# Power.net
KiCad netlist of a schematic drawn in Altium Designer
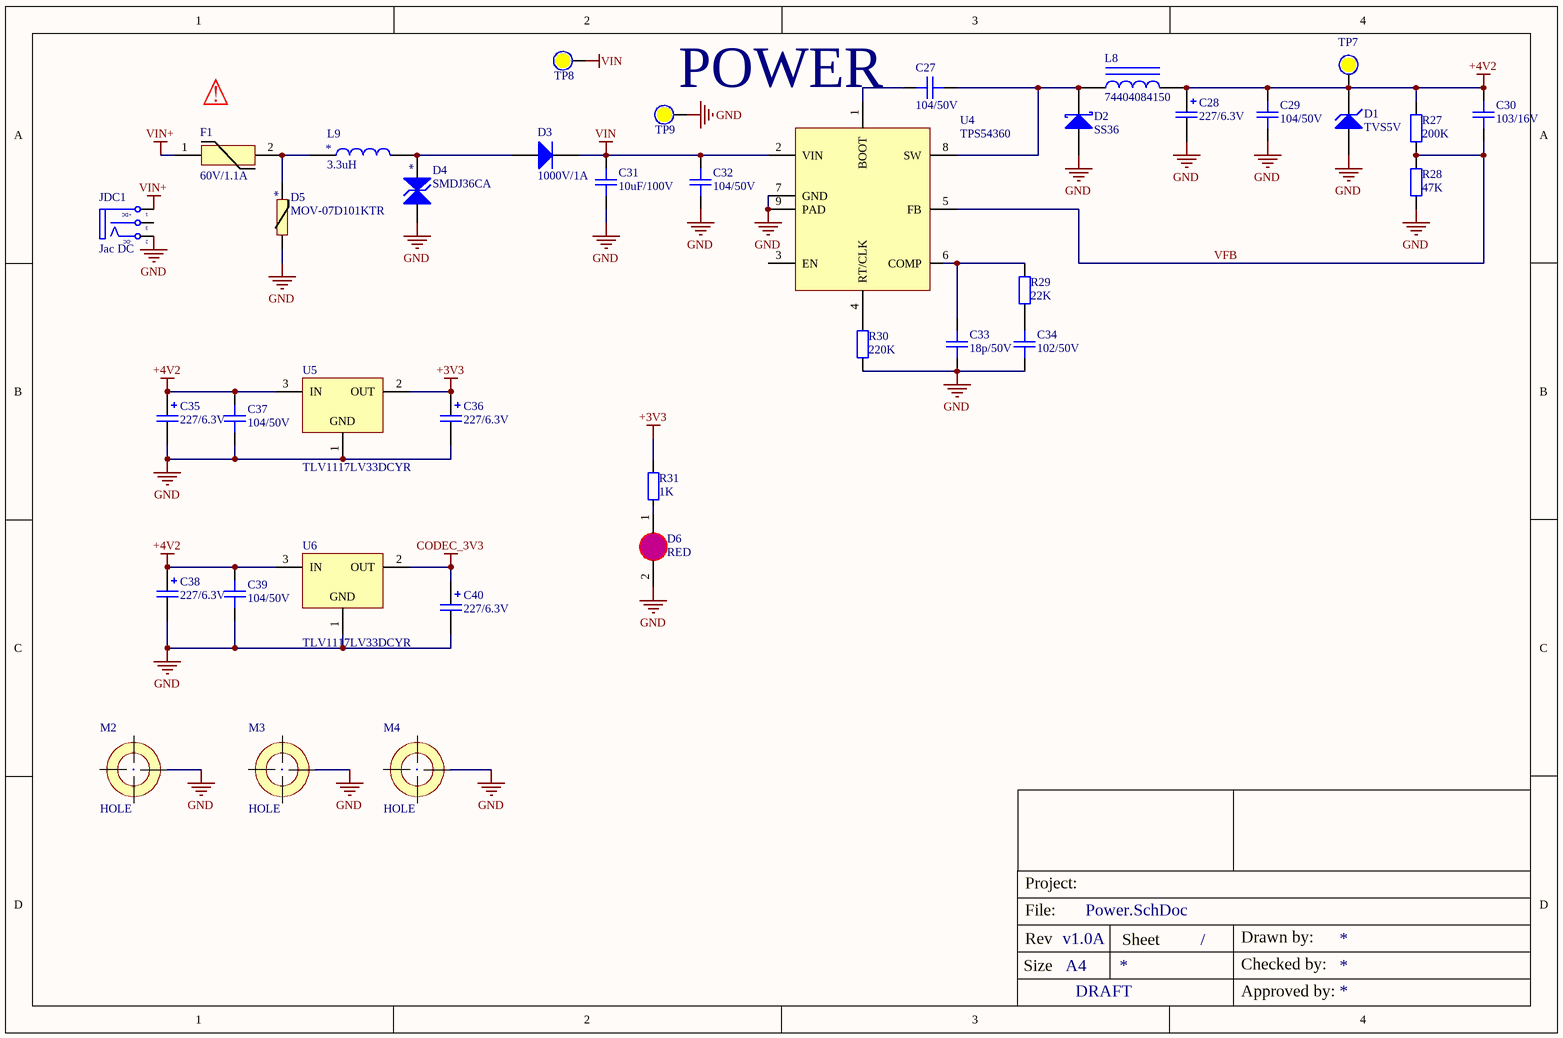
[diagram p0: Power.SchDoc]

(export (version "E")
  (design (tool "Eeschema 10.0.6"))
  (components
    (comp (ref "C27")
      (value "104/50V")
      (footprint "CAPC-0603 (1608)")
      (description "CAP CER 0.1uF 50V 10% X7R 0603")
      (fields (field (name "MPN") "C0603C104K5RACTU"))
      (libsource (lib "01.Passives") (part "C0603C104K5RACTU"))
    )
    (comp (ref "C28")
      (value "227/6.3V")
      (footprint "CAP_TANTAL_1210(3528)")
      (description "CAP TANT POLY 220uF 20% 6.3V 3528 35mOhm ESR")
      (fields (field (name "MPN") "T520B227M006ATE035"))
      (libsource (lib "01.Passives") (part "T520B227M006ATE035"))
    )
    (comp (ref "C29")
      (value "104/50V")
      (footprint "CAPC-0603 (1608)")
      (description "CAP CER 0.1uF 50V 10% X7R 0603")
      (fields (field (name "MPN") "C0603C104K5RACTU"))
      (libsource (lib "01.Passives") (part "C0603C104K5RACTU"))
    )
    (comp (ref "C30")
      (value "103/16V")
      (footprint "CAPC-0603 (1608)")
      (description "CAP CER 10nF 16V 10% X7R 0603")
      (fields (field (name "MPN") "CC0603KRX7R7BB103"))
      (libsource (lib "01.Passives") (part "CC0603KRX7R7BB103"))
    )
    (comp (ref "C31")
      (value "10uF/100V")
      (footprint "CAPC-2220 (5750)")
      (description "CAP CER 10UF 100V X7R 2220")
      (fields (field (name "MPN") "22201C106MAT2A") (field (name "MFR") "AVX Corporation"))
      (libsource (lib "01.Passives") (part "22201C106MAT2A"))
    )
    (comp (ref "C32")
      (value "104/50V")
      (footprint "CAPC-0603 (1608)")
      (description "CAP CER 0.1uF 50V 10% X7R 0603")
      (fields (field (name "MPN") "C0603C104K5RACTU"))
      (libsource (lib "01.Passives") (part "C0603C104K5RACTU"))
    )
    (comp (ref "C33")
      (value "18p/50V")
      (footprint "CAPC-0603 (1608)")
      (description "CAP CER 18pF 5% 50V C0G/NP0 0603")
      (fields (field (name "MPN") "CL10C180JB8NNNC"))
      (libsource (lib "01.Passives") (part "CL10C180JB8NNNC"))
    )
    (comp (ref "C34")
      (value "102/50V")
      (footprint "CAPC-0603 (1608)")
      (description "CAP CER 1nF 50V 10% X7R 0603")
      (fields (field (name "MPN") "C0603C102K5RACTU"))
      (libsource (lib "01.Passives") (part "C0603C102K5RACTU"))
    )
    (comp (ref "C35")
      (value "227/6.3V")
      (footprint "CAP_TANTAL_1210(3528)")
      (description "CAP TANT POLY 220uF 20% 6.3V 3528 35mOhm ESR")
      (fields (field (name "MPN") "T520B227M006ATE035"))
      (libsource (lib "lib") (part "T520B227M006ATE035"))
    )
    (comp (ref "C36")
      (value "227/6.3V")
      (footprint "CAP_TANTAL_1210(3528)")
      (description "CAP TANT POLY 220uF 20% 6.3V 3528 35mOhm ESR")
      (fields (field (name "MPN") "T520B227M006ATE035"))
      (libsource (lib "lib") (part "T520B227M006ATE035"))
    )
    (comp (ref "C37")
      (value "104/50V")
      (footprint "CAPC-0603 (1608)")
      (description "CAP CER 0.1uF 50V 10% X7R 0603")
      (fields (field (name "MPN") "C0603C104K5RACTU"))
      (libsource (lib "lib") (part "C0603C104K5RACTU"))
    )
    (comp (ref "C38")
      (value "227/6.3V")
      (footprint "CAP_TANTAL_1210(3528)")
      (description "CAP TANT POLY 220uF 20% 6.3V 3528 35mOhm ESR")
      (fields (field (name "MPN") "T520B227M006ATE035"))
      (libsource (lib "lib") (part "T520B227M006ATE035"))
    )
    (comp (ref "C39")
      (value "104/50V")
      (footprint "CAPC-0603 (1608)")
      (description "CAP CER 0.1uF 50V 10% X7R 0603")
      (fields (field (name "MPN") "C0603C104K5RACTU"))
      (libsource (lib "lib") (part "C0603C104K5RACTU"))
    )
    (comp (ref "C40")
      (value "227/6.3V")
      (footprint "CAP_TANTAL_1210(3528)")
      (description "CAP TANT POLY 220uF 20% 6.3V 3528 35mOhm ESR")
      (fields (field (name "MPN") "T520B227M006ATE035"))
      (libsource (lib "lib") (part "T520B227M006ATE035"))
    )
    (comp (ref "D1")
      (value "TVS5V")
      (footprint "DIODE_DO214AC_SMA")
      (description "DIODE TVS 5VWM 9.2VC SMA")
      (fields (field (name "MPN") "SMAJ5.0A-E3/61"))
      (libsource (lib "03.Semiconductor") (part "SMAJ5.0A-E3/61"))
    )
    (comp (ref "D2")
      (value "SS36")
      (footprint "DIODE_DO214AC_SMA")
      (description "DIODE SCHOTTKY 60V 3A DO214AC")
      (libsource (lib "03.Semiconductor") (part "B340A-E3/61T"))
    )
    (comp (ref "D3")
      (value "1000V/1A")
      (footprint "DIODE_DO214AC_SMA")
      (description "DIODE GEN PURP 1KV 1A SMA")
      (fields (field (name "MPN") "MRA4007T3G"))
      (libsource (lib "03.Semiconductor") (part "1N4007_SMA"))
    )
    (comp (ref "D4")
      (value "SMDJ36CA")
      (footprint "DIODE_DO214AB_SMC")
      (description "DIODE TVS 36VWM 58.1VC 3KW SMD")
      (libsource (lib "03.Semiconductor") (part "SMDJ36CA"))
    )
    (comp (ref "D5")
      (value "MOV-07D101KTR")
      (footprint "MOV-07D101KTR")
      (description "VARISTOR 100V 1.2KA DISC 7MM")
      (libsource (lib "02.Power-Protection") (part "MOV-07D101KTR"))
    )
    (comp (ref "D6")
      (value "RED")
      (footprint "LED_0805_RED")
      (description "LED RED CLEAR 0805 SMD")
      (fields (field (name "MPN") "17-215SURC/S530-A3/TR8"))
      (libsource (lib "03.Semiconductor") (part "17-215SURC/S530-A3/TR8"))
    )
    (comp (ref "F1")
      (value "60V/1.1A")
      (footprint "RKEF110")
      (description "PTC RESET FUSE 60V 1.1A RADIAL")
      (fields (field (name "MPN") "RKEF110") (field (name "MFR") "Littelfuse Inc."))
      (libsource (lib "02.Power-Protection") (part "RKEF110"))
    )
    (comp (ref "JDC1")
      (value "Jac DC")
      (footprint "DC0")
      (description "Jac DC input")
      (libsource (lib "APESLAB") (part "DCIN"))
    )
    (comp (ref "L8")
      (value "74404084150")
      (footprint "IND-74404084150")
      (description "FIXED IND 15UH 2.6A 47 MOHM SMD")
      (fields (field (name "MFR") "Würth Elektronik"))
      (libsource (lib "01.Passives") (part "SRR1260-150MCT-ND"))
    )
    (comp (ref "L9")
      (value "3.3uH")
      (footprint "IND-CD74-7x7x4MM")
      (description "IND-FIXED 3.3uH CD74 7.4 x 7.4 x 4 MM")
      (fields (field (name "MPN") "CD74_3U3"))
      (libsource (lib "01.Passives") (part "CD74_3U3"))
    )
    (comp (ref "M2")
      (value "HOLE")
      (footprint "HOLE_3MM_6MM")
      (description "3mm/5mm")
      (fields (field (name "MPN") "None"))
      (libsource (lib "08.Miscellaneous") (part "HOLE_3_5"))
    )
    (comp (ref "M3")
      (value "HOLE")
      (footprint "HOLE_3MM_6MM")
      (description "3mm/5mm")
      (fields (field (name "MPN") "None"))
      (libsource (lib "08.Miscellaneous") (part "HOLE_3_5"))
    )
    (comp (ref "M4")
      (value "HOLE")
      (footprint "HOLE_3MM_6MM")
      (description "3mm/5mm")
      (fields (field (name "MPN") "None"))
      (libsource (lib "08.Miscellaneous") (part "HOLE_3_5"))
    )
    (comp (ref "R27")
      (value "200K")
      (footprint "RESC-0603 (1608)")
      (description "RES SMD 200K OHM 1% 1/10W 0603")
      (fields (field (name "MPN") "RC0603FR-07200KL"))
      (libsource (lib "01.Passives") (part "RC0603FR-07220KL"))
    )
    (comp (ref "R28")
      (value "47K")
      (footprint "RESC-0603 (1608)")
      (description "RES SMD 47K OHM 1% 1/10W 0603")
      (fields (field (name "MPN") "RC0603FR0747KL"))
      (libsource (lib "01.Passives") (part "RC0603FR0747KL"))
    )
    (comp (ref "R29")
      (value "22K")
      (footprint "RESC-0603 (1608)")
      (description "RES SMD 22K OHM 1% 1/10W 0603")
      (fields (field (name "MPN") "RC0603FR-0722KL"))
      (libsource (lib "01.Passives") (part "RC0603FR-0722KL"))
    )
    (comp (ref "R30")
      (value "220K")
      (footprint "RESC-0603 (1608)")
      (description "RES SMD 220K OHM 1% 1/10W 0603")
      (fields (field (name "MPN") "RC0603FR-07220KL"))
      (libsource (lib "01.Passives") (part "RC0603FR-07220KL"))
    )
    (comp (ref "R31")
      (value "1K")
      (footprint "RESC-0603 (1608)")
      (description "RES SMD 1 KOHM 1% 1/10W 0603")
      (fields (field (name "MPN") "RC0603FR-071KL"))
      (libsource (lib "01.Passives") (part "RC0603FR-071KL"))
    )
    (comp (ref "TP7")
      (value "~")
      (footprint "Test Point 1.5 MM")
      (description "Test Point")
      (libsource (lib "") (part "Test Point_1"))
    )
    (comp (ref "TP8")
      (value "~")
      (footprint "Test Point 1.5 MM")
      (description "Test Point")
      (libsource (lib "08.Miscellaneous") (part "Test Point"))
    )
    (comp (ref "TP9")
      (value "~")
      (footprint "Test Point 1.5 MM")
      (description "Test Point")
      (libsource (lib "08.Miscellaneous") (part "Test Point"))
    )
    (comp (ref "U4")
      (value "TPS54360")
      (footprint "SOIC8 - POWER")
      (description "60 V Input, 3.5 A, step down regulator with an integrated high side MOSFET")
      (libsource (lib "05.IC") (part "TPS54360"))
    )
    (comp (ref "U5")
      (value "TLV1117LV33DCYR")
      (footprint "SOT-223-4")
      (fields (field (name "MFR") "Texas Instruments"))
      (libsource (lib "05.IC") (part "TLV1117LV33"))
    )
    (comp (ref "U6")
      (value "TLV1117LV33DCYR")
      (footprint "SOT-223-4")
      (fields (field (name "MFR") "Texas Instruments"))
      (libsource (lib "05.IC") (part "TLV1117LV33"))
    )
  )
  (nets
    (net (code "1") (name "+3V3") (class "Default")
      (node (ref "C36") (pin "1") (pinfunction "1_1") (pintype "passive"))
      (node (ref "R31") (pin "2") (pinfunction "2_2") (pintype "passive"))
      (node (ref "U5") (pin "2") (pinfunction "OUT_2") (pintype "power_in"))
    )
    (net (code "2") (name "+4V2") (class "Default")
      (node (ref "C28") (pin "1") (pinfunction "1_1") (pintype "passive"))
      (node (ref "C29") (pin "2") (pinfunction "2_2") (pintype "passive"))
      (node (ref "C30") (pin "2") (pinfunction "2_2") (pintype "passive"))
      (node (ref "C35") (pin "1") (pinfunction "1_1") (pintype "passive"))
      (node (ref "C37") (pin "1") (pinfunction "1_1") (pintype "passive"))
      (node (ref "C38") (pin "1") (pinfunction "1_1") (pintype "passive"))
      (node (ref "C39") (pin "1") (pinfunction "1_1") (pintype "passive"))
      (node (ref "D1") (pin "2") (pinfunction "K_2") (pintype "passive"))
      (node (ref "L8") (pin "2") (pinfunction "2_2") (pintype "passive"))
      (node (ref "R27") (pin "2") (pinfunction "2_2") (pintype "passive"))
      (node (ref "TP7") (pin "0") (pinfunction "0_0") (pintype "passive"))
      (node (ref "U5") (pin "3") (pinfunction "IN_3") (pintype "power_in"))
      (node (ref "U6") (pin "3") (pinfunction "IN_3") (pintype "power_in"))
    )
    (net (code "3") (name "/VFB") (class "Default")
      (node (ref "C30") (pin "1") (pinfunction "1_1") (pintype "passive"))
      (node (ref "R27") (pin "1") (pinfunction "1_1") (pintype "passive"))
      (node (ref "R28") (pin "2") (pinfunction "2_2") (pintype "passive"))
      (node (ref "U4") (pin "5") (pinfunction "FB_5") (pintype "power_in"))
    )
    (net (code "4") (name "CODEC_3V3") (class "Default")
      (node (ref "C40") (pin "1") (pinfunction "1_1") (pintype "passive"))
      (node (ref "U6") (pin "2") (pinfunction "OUT_2") (pintype "power_in"))
    )
    (net (code "5") (name "GND") (class "Default")
      (node (ref "C28") (pin "2") (pinfunction "2_2") (pintype "passive"))
      (node (ref "C29") (pin "1") (pinfunction "1_1") (pintype "passive"))
      (node (ref "C31") (pin "1") (pinfunction "1_1") (pintype "passive"))
      (node (ref "C32") (pin "1") (pinfunction "1_1") (pintype "passive"))
      (node (ref "C33") (pin "1") (pinfunction "1_1") (pintype "passive"))
      (node (ref "C34") (pin "1") (pinfunction "1_1") (pintype "passive"))
      (node (ref "C35") (pin "2") (pinfunction "2_2") (pintype "passive"))
      (node (ref "C36") (pin "2") (pinfunction "2_2") (pintype "passive"))
      (node (ref "C37") (pin "2") (pinfunction "2_2") (pintype "passive"))
      (node (ref "C38") (pin "2") (pinfunction "2_2") (pintype "passive"))
      (node (ref "C39") (pin "2") (pinfunction "2_2") (pintype "passive"))
      (node (ref "C40") (pin "2") (pinfunction "2_2") (pintype "passive"))
      (node (ref "D1") (pin "1") (pinfunction "A_1") (pintype "passive"))
      (node (ref "D2") (pin "1") (pinfunction "A_1") (pintype "passive"))
      (node (ref "D4") (pin "1") (pinfunction "A_1") (pintype "passive"))
      (node (ref "D5") (pin "1") (pinfunction "A_1") (pintype "passive"))
      (node (ref "D6") (pin "2") (pinfunction "K_2") (pintype "passive"))
      (node (ref "JDC1") (pin "2") (pinfunction "TN_2") (pintype "passive"))
      (node (ref "R28") (pin "1") (pinfunction "1_1") (pintype "passive"))
      (node (ref "R30") (pin "1") (pinfunction "1_1") (pintype "passive"))
      (node (ref "TP9") (pin "0") (pinfunction "0_0") (pintype "passive"))
      (node (ref "U4") (pin "7") (pinfunction "GND_7") (pintype "power_in"))
      (node (ref "U4") (pin "9") (pinfunction "PAD_9") (pintype "power_in"))
      (node (ref "U5") (pin "1") (pinfunction "GND_1") (pintype "power_in"))
      (node (ref "U6") (pin "1") (pinfunction "GND_1") (pintype "power_in"))
    )
    (net (code "6") (name "Net-(C34-Pad2)") (class "Default")
      (node (ref "C34") (pin "2") (pinfunction "2_2") (pintype "passive"))
      (node (ref "R29") (pin "1") (pinfunction "1_1") (pintype "passive"))
    )
    (net (code "7") (name "Net-(D2-K)") (class "Default")
      (node (ref "C27") (pin "1") (pinfunction "1_1") (pintype "passive"))
      (node (ref "D2") (pin "2") (pinfunction "K_2") (pintype "passive"))
      (node (ref "L8") (pin "1") (pinfunction "1_1") (pintype "passive"))
      (node (ref "U4") (pin "8") (pinfunction "SW_8") (pintype "power_in"))
    )
    (net (code "8") (name "Net-(D3-A)") (class "Default")
      (node (ref "D3") (pin "1") (pinfunction "A_1") (pintype "passive"))
      (node (ref "D4") (pin "2") (pinfunction "K_2") (pintype "passive"))
      (node (ref "L9") (pin "2") (pinfunction "2_2") (pintype "passive"))
    )
    (net (code "9") (name "Net-(D5-K)") (class "Default")
      (node (ref "D5") (pin "2") (pinfunction "K_2") (pintype "passive"))
      (node (ref "F1") (pin "2") (pinfunction "2_2") (pintype "passive"))
      (node (ref "L9") (pin "1") (pinfunction "1_1") (pintype "passive"))
    )
    (net (code "10") (name "Net-(D6-A)") (class "Default")
      (node (ref "D6") (pin "1") (pinfunction "A_1") (pintype "passive"))
      (node (ref "R31") (pin "1") (pinfunction "1_1") (pintype "passive"))
    )
    (net (code "11") (name "Net-(U4-BOOT)") (class "Default")
      (node (ref "C27") (pin "2") (pinfunction "2_2") (pintype "passive"))
      (node (ref "U4") (pin "1") (pinfunction "BOOT_1") (pintype "power_in"))
    )
    (net (code "12") (name "Net-(U4-COMP)") (class "Default")
      (node (ref "C33") (pin "2") (pinfunction "2_2") (pintype "passive"))
      (node (ref "R29") (pin "2") (pinfunction "2_2") (pintype "passive"))
      (node (ref "U4") (pin "6") (pinfunction "COMP_6") (pintype "power_in"))
    )
    (net (code "13") (name "Net-(U4-RT{slash}CLK)") (class "Default")
      (node (ref "R30") (pin "2") (pinfunction "2_2") (pintype "passive"))
      (node (ref "U4") (pin "4") (pinfunction "RT/CLK_4") (pintype "power_in"))
    )
    (net (code "14") (name "VIN") (class "Default")
      (node (ref "C31") (pin "2") (pinfunction "2_2") (pintype "passive"))
      (node (ref "C32") (pin "2") (pinfunction "2_2") (pintype "passive"))
      (node (ref "D3") (pin "2") (pinfunction "K_2") (pintype "passive"))
      (node (ref "TP8") (pin "0") (pinfunction "0_0") (pintype "passive"))
      (node (ref "U4") (pin "2") (pinfunction "VIN_2") (pintype "power_in"))
    )
    (net (code "15") (name "VIN+") (class "Default")
      (node (ref "F1") (pin "1") (pinfunction "1_1") (pintype "passive"))
      (node (ref "JDC1") (pin "1") (pinfunction "T_1") (pintype "passive"))
    )
    (net (code "16") (name "unconnected-(JDC1-S-Pad3)") (class "Default")
      (node (ref "JDC1") (pin "3") (pinfunction "S_3") (pintype "power_in"))
    )
    (net (code "17") (name "unconnected-(U4-EN-Pad3)") (class "Default")
      (node (ref "U4") (pin "3") (pinfunction "EN_3") (pintype "power_in"))
    )
  )
)
